# BW1097_GPIOHDR.net
KiCad netlist of a schematic drawn in Altium Designer
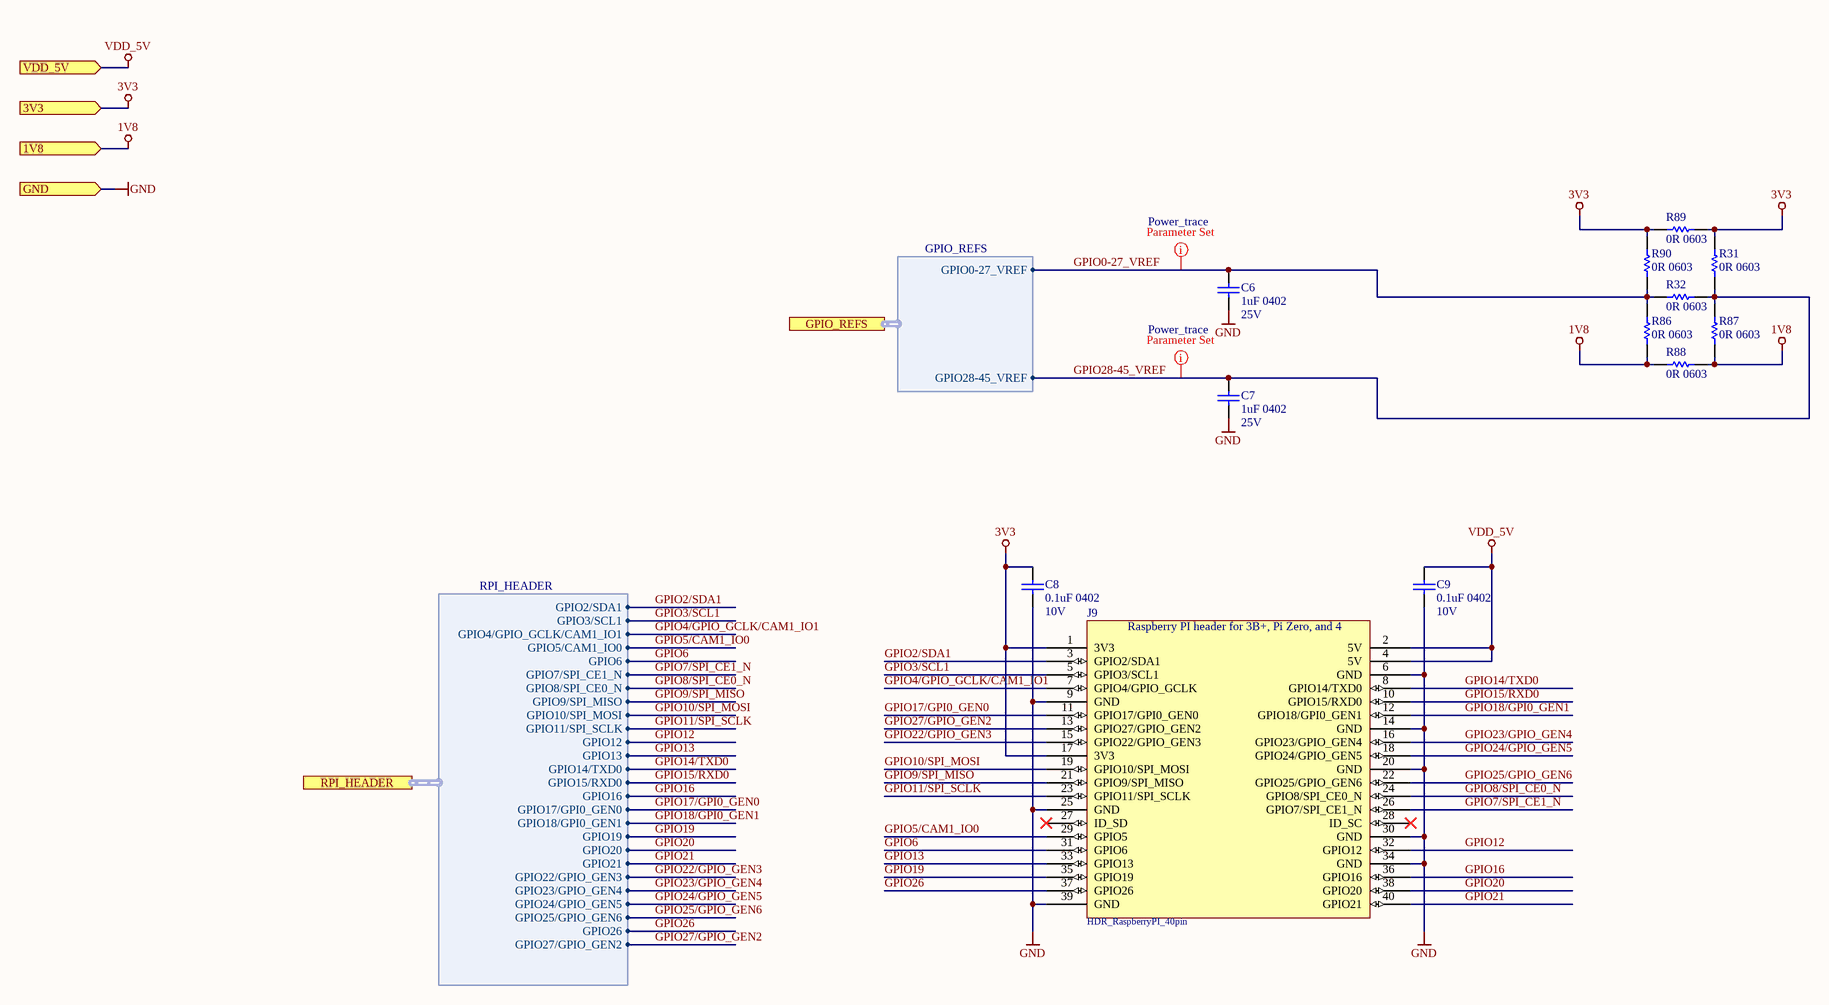
[diagram p0: BW1097_GPIOHDR.SchDoc]

(export (version "E")
  (design (tool "Eeschema 10.0.6"))
  (components
    (comp (ref "C6")
      (value "1uF 0402")
      (footprint "CAP_Altium_Vault_Generic:CAPC0402(1005)70_N")
      (description "CAP CER 1UF 25V X5R 0402 10%")
      (fields
        (field (name "TOLERANCE") "10%")
        (field (name "VOLTAGE") "25V")
        (field (name "VOLTAGE RATING") "25V")
      )
      (libsource (lib "LuxonisMaster") (part "GRM155R61E105KA12D"))
    )
    (comp (ref "C7")
      (value "1uF 0402")
      (footprint "CAP_Altium_Vault_Generic:CAPC0402(1005)70_N")
      (description "CAP CER 1UF 25V X5R 0402 10%")
      (fields
        (field (name "TOLERANCE") "10%")
        (field (name "VOLTAGE") "25V")
        (field (name "VOLTAGE RATING") "25V")
      )
      (libsource (lib "LuxonisMaster") (part "GRM155R61E105KA12D"))
    )
    (comp (ref "C8")
      (value "0.1uF 0402")
      (footprint "CAP_Altium_Vault_Generic:CAPC0402(1005)70_N")
      (description "CAP CER 0.1UF 10V X7R 0402 5%")
      (fields (field (name "TOLERANCE") "5%") (field (name "VOLTAGE RATING") "10V"))
      (libsource (lib "LuxonisMaster") (part "GRM155R71A104JA01D"))
    )
    (comp (ref "C9")
      (value "0.1uF 0402")
      (footprint "CAP_Altium_Vault_Generic:CAPC0402(1005)70_N")
      (description "CAP CER 0.1UF 10V X7R 0402 5%")
      (fields (field (name "TOLERANCE") "5%") (field (name "VOLTAGE RATING") "10V"))
      (libsource (lib "LuxonisMaster") (part "GRM155R71A104JA01D"))
    )
    (comp (ref "J9")
      (value "HDR_RaspberryPI_40pin")
      (footprint "LuxonisMaster:61304021121")
      (description "CONN HEADER VERT 40POS 2.54MM THT HDR_RaspberryPI_40pin")
      (fields
        (field (name "MANUFACTURER") "Wurth Elektronik")
        (field (name "PART NUMBER") "61304021121")
        (field (name "PUBLISHER") "WurthElektronik")
      )
      (libsource (lib "LuxonisMaster") (part "61304021121_RPI_40pin"))
    )
    (comp (ref "R31")
      (value "0R 0603")
      (footprint "RES_Altium_Vault_Generic:RESC0603(1608)_N")
      (fields (field (name "TOLERANCE") "5%"))
      (libsource (lib "LuxonisMaster") (part "CRCW06030000Z0EA"))
    )
    (comp (ref "R32")
      (value "0R 0603")
      (footprint "RES_Altium_Vault_Generic:RESC0603(1608)_N")
      (fields (field (name "TOLERANCE") "5%"))
      (libsource (lib "LuxonisMaster") (part "CRCW06030000Z0EA"))
    )
    (comp (ref "R86")
      (value "0R 0603")
      (footprint "RES_Altium_Vault_Generic:RESC0603(1608)_N")
      (fields (field (name "TOLERANCE") "5%"))
      (libsource (lib "LuxonisMaster") (part "CRCW06030000Z0EA"))
    )
    (comp (ref "R87")
      (value "0R 0603")
      (footprint "RES_Altium_Vault_Generic:RESC0603(1608)_N")
      (fields (field (name "TOLERANCE") "5%"))
      (libsource (lib "LuxonisMaster") (part "CRCW06030000Z0EA"))
    )
    (comp (ref "R88")
      (value "0R 0603")
      (footprint "RES_Altium_Vault_Generic:RESC0603(1608)_N")
      (fields (field (name "TOLERANCE") "5%"))
      (libsource (lib "LuxonisMaster") (part "CRCW06030000Z0EA"))
    )
    (comp (ref "R89")
      (value "0R 0603")
      (footprint "RES_Altium_Vault_Generic:RESC0603(1608)_N")
      (fields (field (name "TOLERANCE") "5%"))
      (libsource (lib "LuxonisMaster") (part "CRCW06030000Z0EA"))
    )
    (comp (ref "R90")
      (value "0R 0603")
      (footprint "RES_Altium_Vault_Generic:RESC0603(1608)_N")
      (fields (field (name "TOLERANCE") "5%"))
      (libsource (lib "LuxonisMaster") (part "CRCW06030000Z0EA"))
    )
  )
  (nets
    (net (code "3") (name "/GPIO0-27_VREF") (class "Default")
      (node (ref "C6") (pin "2") (pinfunction "2_2") (pintype "passive"))
      (node (ref "R32") (pin "2") (pinfunction "2_2") (pintype "passive"))
      (node (ref "R86") (pin "2") (pinfunction "2_2") (pintype "passive"))
      (node (ref "R90") (pin "1") (pinfunction "1_1") (pintype "passive"))
    )
    (net (code "4") (name "/GPIO2{slash}SDA1") (class "Default")
      (node (ref "J9") (pin "3") (pinfunction "GPIO2/SDA1_3") (pintype "bidirectional"))
    )
    (net (code "5") (name "/GPIO3{slash}SCL1") (class "Default")
      (node (ref "J9") (pin "5") (pinfunction "GPIO3/SCL1_5") (pintype "bidirectional"))
    )
    (net (code "6") (name "/GPIO4{slash}GPIO_GCLK{slash}CAM1_IO1") (class "Default")
      (node (ref "J9") (pin "7") (pinfunction "GPIO4/GPIO_GCLK_7") (pintype "bidirectional"))
    )
    (net (code "7") (name "/GPIO5{slash}CAM1_IO0") (class "Default")
      (node (ref "J9") (pin "29") (pinfunction "GPIO5_29") (pintype "bidirectional"))
    )
    (net (code "8") (name "/GPIO6") (class "Default")
      (node (ref "J9") (pin "31") (pinfunction "GPIO6_31") (pintype "bidirectional"))
    )
    (net (code "9") (name "/GPIO7{slash}SPI_CE1_N") (class "Default")
      (node (ref "J9") (pin "26") (pinfunction "GPIO7/SPI_CE1_N_26") (pintype "bidirectional"))
    )
    (net (code "10") (name "/GPIO8{slash}SPI_CE0_N") (class "Default")
      (node (ref "J9") (pin "24") (pinfunction "GPIO8/SPI_CE0_N_24") (pintype "bidirectional"))
    )
    (net (code "11") (name "/GPIO9{slash}SPI_MISO") (class "Default")
      (node (ref "J9") (pin "21") (pinfunction "GPIO9/SPI_MISO_21") (pintype "bidirectional"))
    )
    (net (code "12") (name "/GPIO10{slash}SPI_MOSI") (class "Default")
      (node (ref "J9") (pin "19") (pinfunction "GPIO10/SPI_MOSI_19") (pintype "bidirectional"))
    )
    (net (code "13") (name "/GPIO11{slash}SPI_SCLK") (class "Default")
      (node (ref "J9") (pin "23") (pinfunction "GPIO11/SPI_SCLK_23") (pintype "bidirectional"))
    )
    (net (code "14") (name "/GPIO12") (class "Default")
      (node (ref "J9") (pin "32") (pinfunction "GPIO12_32") (pintype "bidirectional"))
    )
    (net (code "15") (name "/GPIO13") (class "Default")
      (node (ref "J9") (pin "33") (pinfunction "GPIO13_33") (pintype "bidirectional"))
    )
    (net (code "16") (name "/GPIO14{slash}TXD0") (class "Default")
      (node (ref "J9") (pin "8") (pinfunction "GPIO14/TXD0_8") (pintype "bidirectional"))
    )
    (net (code "17") (name "/GPIO15{slash}RXD0") (class "Default")
      (node (ref "J9") (pin "10") (pinfunction "GPIO15/RXD0_10") (pintype "bidirectional"))
    )
    (net (code "18") (name "/GPIO16") (class "Default")
      (node (ref "J9") (pin "36") (pinfunction "GPIO16_36") (pintype "bidirectional"))
    )
    (net (code "19") (name "/GPIO17{slash}GPI0_GEN0") (class "Default")
      (node (ref "J9") (pin "11") (pinfunction "GPIO17/GPI0_GEN0_11") (pintype "bidirectional"))
    )
    (net (code "20") (name "/GPIO18{slash}GPI0_GEN1") (class "Default")
      (node (ref "J9") (pin "12") (pinfunction "GPIO18/GPI0_GEN1_12") (pintype "bidirectional"))
    )
    (net (code "21") (name "/GPIO19") (class "Default")
      (node (ref "J9") (pin "35") (pinfunction "GPIO19_35") (pintype "bidirectional"))
    )
    (net (code "22") (name "/GPIO20") (class "Default")
      (node (ref "J9") (pin "38") (pinfunction "GPIO20_38") (pintype "bidirectional"))
    )
    (net (code "23") (name "/GPIO21") (class "Default")
      (node (ref "J9") (pin "40") (pinfunction "GPIO21_40") (pintype "bidirectional"))
    )
    (net (code "24") (name "/GPIO22{slash}GPIO_GEN3") (class "Default")
      (node (ref "J9") (pin "15") (pinfunction "GPIO22/GPIO_GEN3_15") (pintype "bidirectional"))
    )
    (net (code "25") (name "/GPIO23{slash}GPIO_GEN4") (class "Default")
      (node (ref "J9") (pin "16") (pinfunction "GPIO23/GPIO_GEN4_16") (pintype "bidirectional"))
    )
    (net (code "26") (name "/GPIO24{slash}GPIO_GEN5") (class "Default")
      (node (ref "J9") (pin "18") (pinfunction "GPIO24/GPIO_GEN5_18") (pintype "bidirectional"))
    )
    (net (code "27") (name "/GPIO25{slash}GPIO_GEN6") (class "Default")
      (node (ref "J9") (pin "22") (pinfunction "GPIO25/GPIO_GEN6_22") (pintype "bidirectional"))
    )
    (net (code "28") (name "/GPIO26") (class "Default")
      (node (ref "J9") (pin "37") (pinfunction "GPIO26_37") (pintype "bidirectional"))
    )
    (net (code "29") (name "/GPIO27{slash}GPIO_GEN2") (class "Default")
      (node (ref "J9") (pin "13") (pinfunction "GPIO27/GPIO_GEN2_13") (pintype "bidirectional"))
    )
    (net (code "30") (name "/GPIO28-45_VREF") (class "Default")
      (node (ref "C7") (pin "2") (pinfunction "2_2") (pintype "passive"))
      (node (ref "R31") (pin "1") (pinfunction "1_1") (pintype "passive"))
      (node (ref "R32") (pin "1") (pinfunction "1_1") (pintype "passive"))
      (node (ref "R87") (pin "2") (pinfunction "2_2") (pintype "passive"))
    )
    (net (code "33") (name "1V8") (class "Default")
      (node (ref "R86") (pin "1") (pinfunction "1_1") (pintype "passive"))
      (node (ref "R87") (pin "1") (pinfunction "1_1") (pintype "passive"))
      (node (ref "R88") (pin "1") (pinfunction "1_1") (pintype "passive"))
      (node (ref "R88") (pin "2") (pinfunction "2_2") (pintype "passive"))
    )
    (net (code "34") (name "3V3") (class "Default")
      (node (ref "C8") (pin "2") (pinfunction "2_2") (pintype "passive"))
      (node (ref "J9") (pin "1") (pinfunction "3V3_1") (pintype "passive"))
      (node (ref "J9") (pin "17") (pinfunction "3V3_17") (pintype "passive"))
      (node (ref "R31") (pin "2") (pinfunction "2_2") (pintype "passive"))
      (node (ref "R89") (pin "1") (pinfunction "1_1") (pintype "passive"))
      (node (ref "R89") (pin "2") (pinfunction "2_2") (pintype "passive"))
      (node (ref "R90") (pin "2") (pinfunction "2_2") (pintype "passive"))
    )
    (net (code "35") (name "GND") (class "Default")
      (node (ref "C6") (pin "1") (pinfunction "1_1") (pintype "passive"))
      (node (ref "C7") (pin "1") (pinfunction "1_1") (pintype "passive"))
      (node (ref "C8") (pin "1") (pinfunction "1_1") (pintype "passive"))
      (node (ref "C9") (pin "1") (pinfunction "1_1") (pintype "passive"))
      (node (ref "J9") (pin "14") (pinfunction "GND_14") (pintype "passive"))
      (node (ref "J9") (pin "20") (pinfunction "GND_20") (pintype "passive"))
      (node (ref "J9") (pin "25") (pinfunction "GND_25") (pintype "passive"))
      (node (ref "J9") (pin "30") (pinfunction "GND_30") (pintype "passive"))
      (node (ref "J9") (pin "34") (pinfunction "GND_34") (pintype "passive"))
      (node (ref "J9") (pin "39") (pinfunction "GND_39") (pintype "passive"))
      (node (ref "J9") (pin "6") (pinfunction "GND_6") (pintype "passive"))
      (node (ref "J9") (pin "9") (pinfunction "GND_9") (pintype "passive"))
    )
    (net (code "36") (name "VDD_5V") (class "Default")
      (node (ref "C9") (pin "2") (pinfunction "2_2") (pintype "passive"))
      (node (ref "J9") (pin "2") (pinfunction "5V_2") (pintype "passive"))
      (node (ref "J9") (pin "4") (pinfunction "5V_4") (pintype "passive"))
    )
    (net (code "37") (name "unconnected-(J9-ID_SC-Pad28)") (class "Default")
      (node (ref "J9") (pin "28") (pinfunction "ID_SC_28") (pintype "bidirectional+no_connect"))
    )
    (net (code "38") (name "unconnected-(J9-ID_SD-Pad27)") (class "Default")
      (node (ref "J9") (pin "27") (pinfunction "ID_SD_27") (pintype "bidirectional+no_connect"))
    )
  )
)
